# 464421_22-01_RF_Interface.net
KiCad netlist of a schematic drawn in Altium Designer
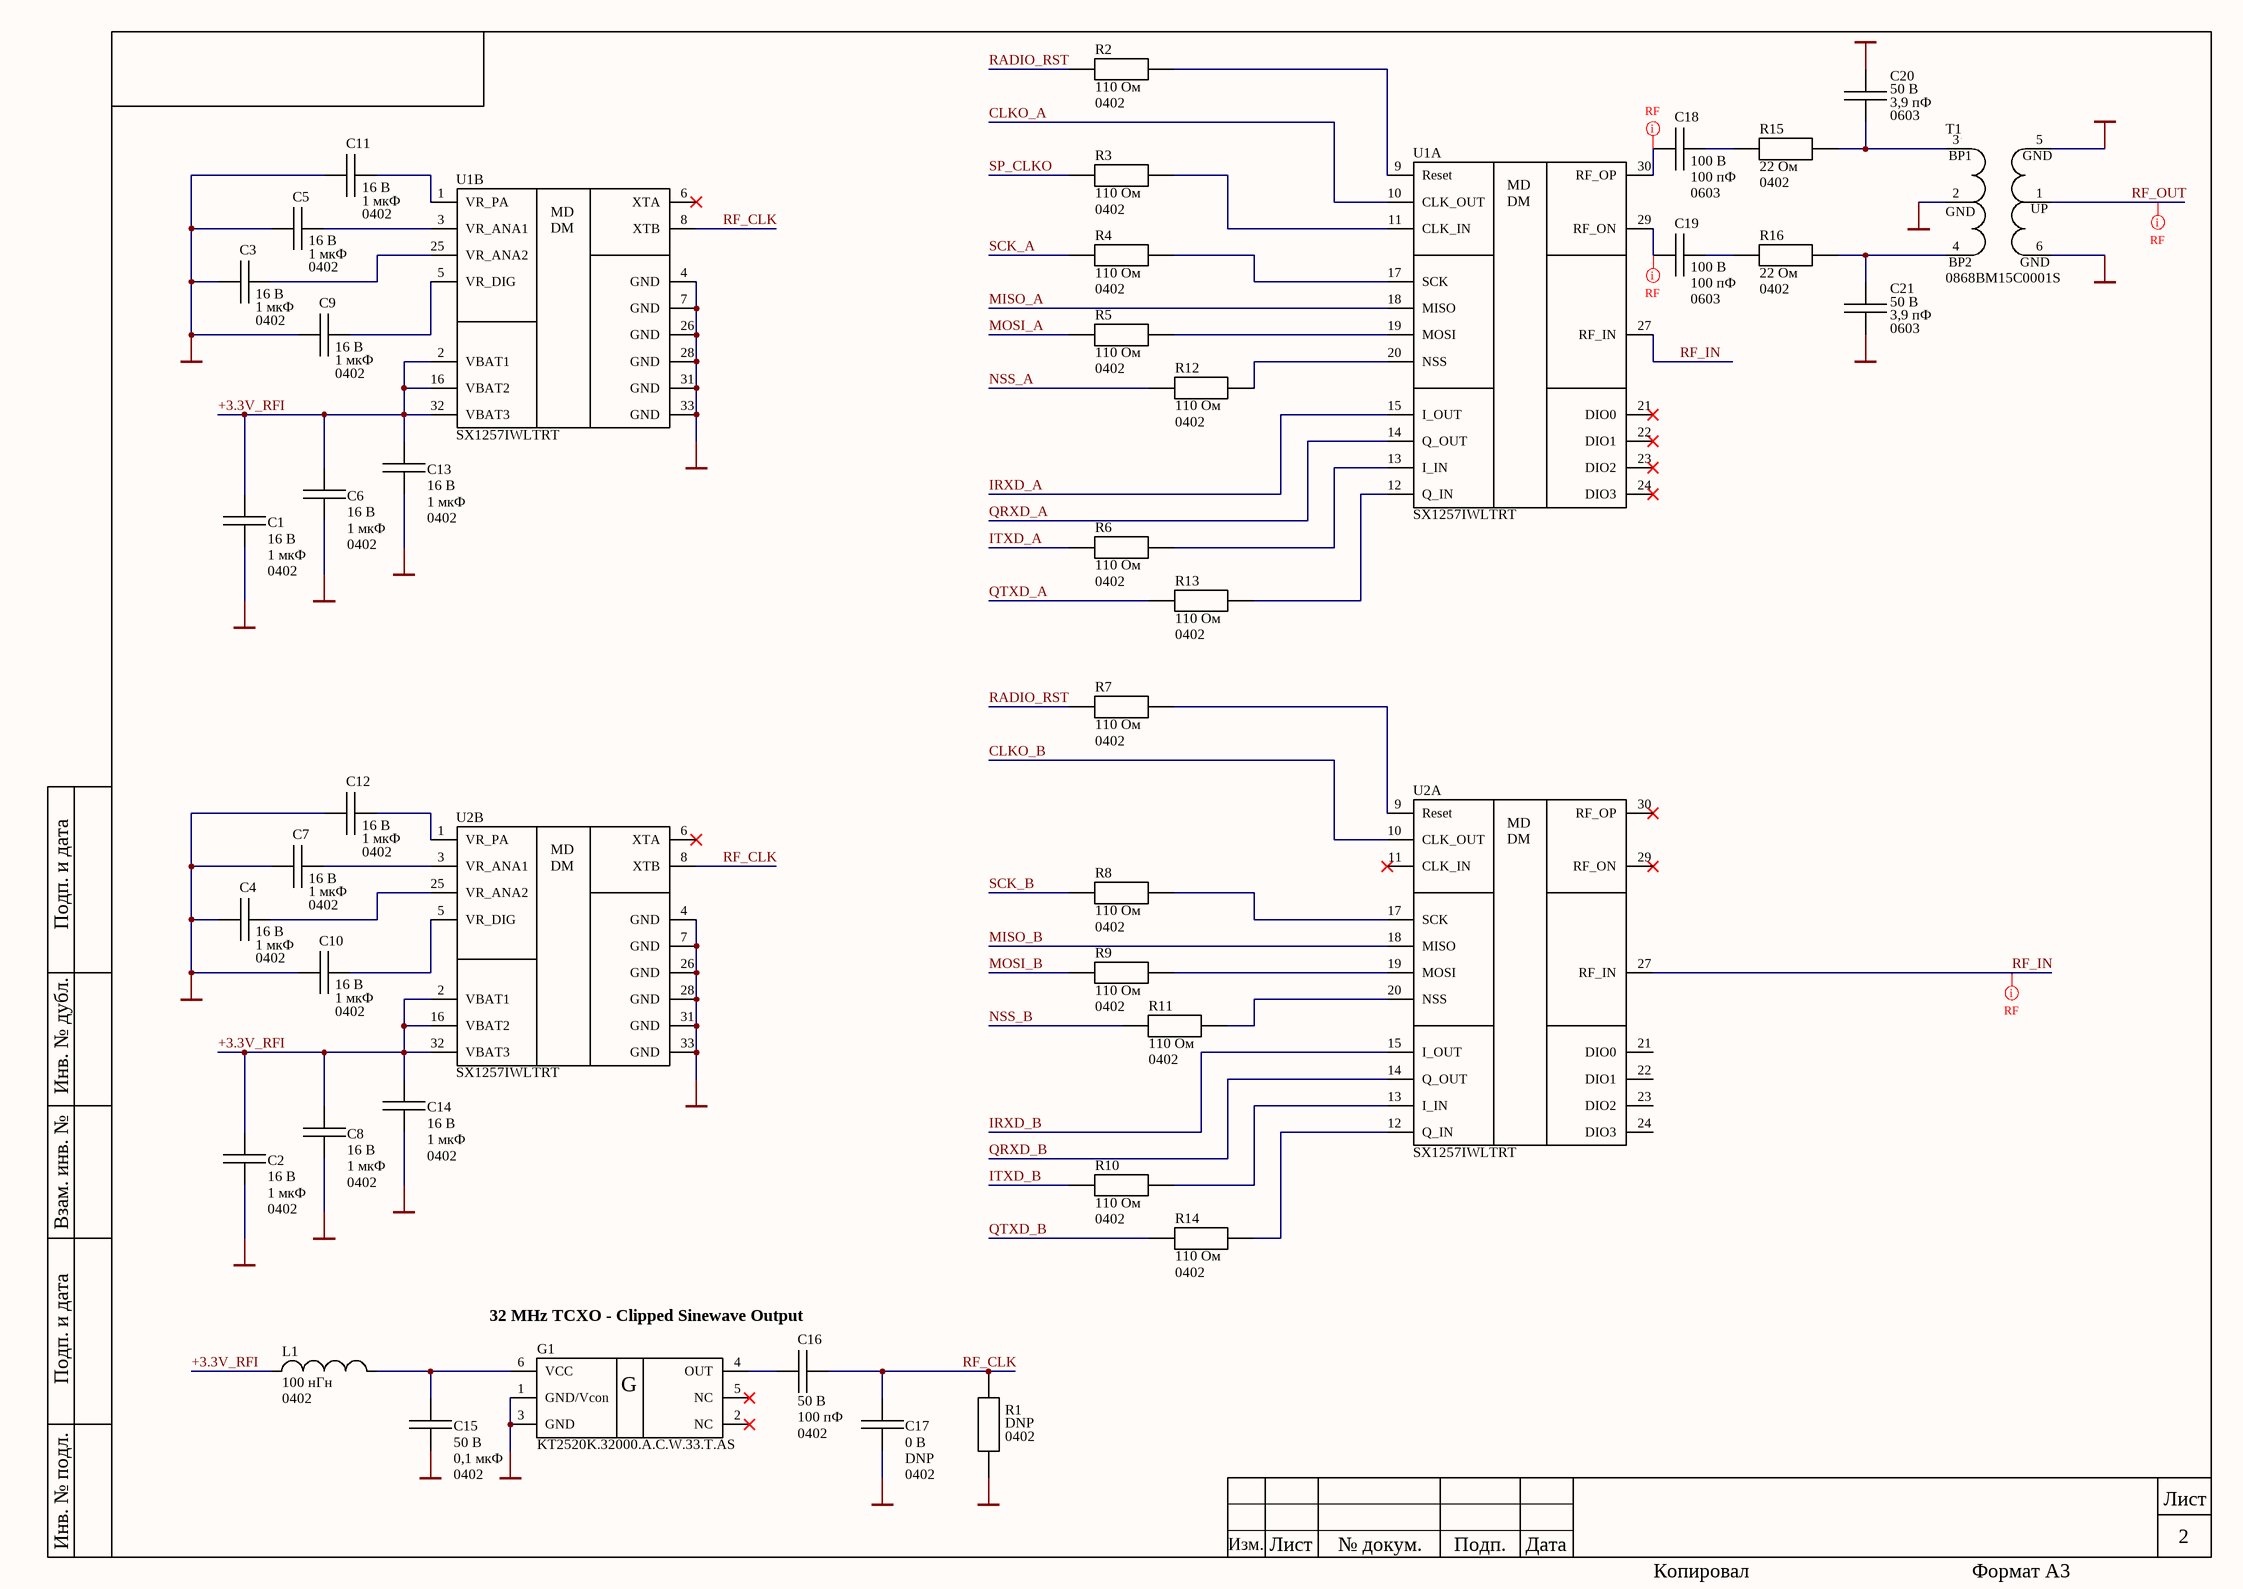
[diagram p0: МПСУ.464421.22-01 RF Interface.SchDoc]

(export (version "E")
  (design (tool "Eeschema 10.0.6"))
  (components
    (comp (ref "C1")
      (value "1 мкФ")
      (footprint "Passive_V2_0:CAPC100X50X55L20N")
      (description "Capacitor 0402")
      (fields
        (field (name "PARTNUMBER") "GRM155R61C105KA12D")
        (field (name "MANUFACTURER") "Murata")
        (field (name "PEAK_CONDITION") "16 В")
        (field (name "PACKAGE") "0402")
        (field (name "DESIGNER") "Свидерский")
      )
      (libsource (lib "Passive_V2_0") (part "C 0402"))
    )
    (comp (ref "C2")
      (value "1 мкФ")
      (footprint "Passive_V2_0:CAPC100X50X55L20N")
      (description "Capacitor 0402")
      (fields
        (field (name "PARTNUMBER") "GRM155R61C105KA12D")
        (field (name "MANUFACTURER") "Murata")
        (field (name "PEAK_CONDITION") "16 В")
        (field (name "PACKAGE") "0402")
        (field (name "DESIGNER") "Свидерский")
      )
      (libsource (lib "Passive_V2_0") (part "C 0402"))
    )
    (comp (ref "C3")
      (value "1 мкФ")
      (footprint "Passive_V2_0:CAPC100X50X55L20N")
      (description "Capacitor 0402")
      (fields
        (field (name "PARTNUMBER") "GRM155R61C105KA12D")
        (field (name "MANUFACTURER") "Murata")
        (field (name "PEAK_CONDITION") "16 В")
        (field (name "PACKAGE") "0402")
        (field (name "DESIGNER") "Свидерский")
      )
      (libsource (lib "Passive_V2_0") (part "C 0402"))
    )
    (comp (ref "C4")
      (value "1 мкФ")
      (footprint "Passive_V2_0:CAPC100X50X55L20N")
      (description "Capacitor 0402")
      (fields
        (field (name "PARTNUMBER") "GRM155R61C105KA12D")
        (field (name "MANUFACTURER") "Murata")
        (field (name "PEAK_CONDITION") "16 В")
        (field (name "PACKAGE") "0402")
        (field (name "DESIGNER") "Свидерский")
      )
      (libsource (lib "Passive_V2_0") (part "C 0402"))
    )
    (comp (ref "C5")
      (value "1 мкФ")
      (footprint "Passive_V2_0:CAPC100X50X55L20N")
      (description "Capacitor 0402")
      (fields
        (field (name "PARTNUMBER") "GRM155R61C105KA12D")
        (field (name "MANUFACTURER") "Murata")
        (field (name "PEAK_CONDITION") "16 В")
        (field (name "PACKAGE") "0402")
        (field (name "DESIGNER") "Свидерский")
      )
      (libsource (lib "Passive_V2_0") (part "C 0402"))
    )
    (comp (ref "C6")
      (value "1 мкФ")
      (footprint "Passive_V2_0:CAPC100X50X55L20N")
      (description "Capacitor 0402")
      (fields
        (field (name "PARTNUMBER") "GRM155R61C105KA12D")
        (field (name "MANUFACTURER") "Murata")
        (field (name "PEAK_CONDITION") "16 В")
        (field (name "PACKAGE") "0402")
        (field (name "DESIGNER") "Свидерский")
      )
      (libsource (lib "Passive_V2_0") (part "C 0402"))
    )
    (comp (ref "C7")
      (value "1 мкФ")
      (footprint "Passive_V2_0:CAPC100X50X55L20N")
      (description "Capacitor 0402")
      (fields
        (field (name "PARTNUMBER") "GRM155R61C105KA12D")
        (field (name "MANUFACTURER") "Murata")
        (field (name "PEAK_CONDITION") "16 В")
        (field (name "PACKAGE") "0402")
        (field (name "DESIGNER") "Свидерский")
      )
      (libsource (lib "Passive_V2_0") (part "C 0402"))
    )
    (comp (ref "C8")
      (value "1 мкФ")
      (footprint "Passive_V2_0:CAPC100X50X55L20N")
      (description "Capacitor 0402")
      (fields
        (field (name "PARTNUMBER") "GRM155R61C105KA12D")
        (field (name "MANUFACTURER") "Murata")
        (field (name "PEAK_CONDITION") "16 В")
        (field (name "PACKAGE") "0402")
        (field (name "DESIGNER") "Свидерский")
      )
      (libsource (lib "Passive_V2_0") (part "C 0402"))
    )
    (comp (ref "C9")
      (value "1 мкФ")
      (footprint "Passive_V2_0:CAPC100X50X55L20N")
      (description "Capacitor 0402")
      (fields
        (field (name "PARTNUMBER") "GRM155R61C105KA12D")
        (field (name "MANUFACTURER") "Murata")
        (field (name "PEAK_CONDITION") "16 В")
        (field (name "PACKAGE") "0402")
        (field (name "DESIGNER") "Свидерский")
      )
      (libsource (lib "Passive_V2_0") (part "C 0402"))
    )
    (comp (ref "C10")
      (value "1 мкФ")
      (footprint "Passive_V2_0:CAPC100X50X55L20N")
      (description "Capacitor 0402")
      (fields
        (field (name "PARTNUMBER") "GRM155R61C105KA12D")
        (field (name "MANUFACTURER") "Murata")
        (field (name "PEAK_CONDITION") "16 В")
        (field (name "PACKAGE") "0402")
        (field (name "DESIGNER") "Свидерский")
      )
      (libsource (lib "Passive_V2_0") (part "C 0402"))
    )
    (comp (ref "C11")
      (value "1 мкФ")
      (footprint "Passive_V2_0:CAPC100X50X55L20N")
      (description "Capacitor 0402")
      (fields
        (field (name "PARTNUMBER") "GRM155R61C105KA12D")
        (field (name "MANUFACTURER") "Murata")
        (field (name "PEAK_CONDITION") "16 В")
        (field (name "PACKAGE") "0402")
        (field (name "DESIGNER") "Свидерский")
      )
      (libsource (lib "Passive_V2_0") (part "C 0402"))
    )
    (comp (ref "C12")
      (value "1 мкФ")
      (footprint "Passive_V2_0:CAPC100X50X55L20N")
      (description "Capacitor 0402")
      (fields
        (field (name "PARTNUMBER") "GRM155R61C105KA12D")
        (field (name "MANUFACTURER") "Murata")
        (field (name "PEAK_CONDITION") "16 В")
        (field (name "PACKAGE") "0402")
        (field (name "DESIGNER") "Свидерский")
      )
      (libsource (lib "Passive_V2_0") (part "C 0402"))
    )
    (comp (ref "C13")
      (value "1 мкФ")
      (footprint "Passive_V2_0:CAPC100X50X55L20N")
      (description "Capacitor 0402")
      (fields
        (field (name "PARTNUMBER") "GRM155R61C105KA12D")
        (field (name "MANUFACTURER") "Murata")
        (field (name "PEAK_CONDITION") "16 В")
        (field (name "PACKAGE") "0402")
        (field (name "DESIGNER") "Свидерский")
      )
      (libsource (lib "Passive_V2_0") (part "C 0402"))
    )
    (comp (ref "C14")
      (value "1 мкФ")
      (footprint "Passive_V2_0:CAPC100X50X55L20N")
      (description "Capacitor 0402")
      (fields
        (field (name "PARTNUMBER") "GRM155R61C105KA12D")
        (field (name "MANUFACTURER") "Murata")
        (field (name "PEAK_CONDITION") "16 В")
        (field (name "PACKAGE") "0402")
        (field (name "DESIGNER") "Свидерский")
      )
      (libsource (lib "Passive_V2_0") (part "C 0402"))
    )
    (comp (ref "C15")
      (value "0,1 мкФ")
      (footprint "Passive_V2_0:CAPC100X50X55L20N")
      (description "Capacitor 0402")
      (fields
        (field (name "PARTNUMBER") "GRM155R71H104KE14J")
        (field (name "MANUFACTURER") "Murata")
        (field (name "PEAK_CONDITION") "50 В")
        (field (name "PACKAGE") "0402")
        (field (name "DESIGNER") "Свидерский")
      )
      (libsource (lib "Passive_V2_0") (part "C 0402"))
    )
    (comp (ref "C16")
      (value "100 пФ")
      (footprint "Passive_V2_0:CAPC100X50X55L20N")
      (description "Capacitor 0402")
      (fields
        (field (name "PARTNUMBER") "GRM1555C1H101JZ01D")
        (field (name "MANUFACTURER") "Murata")
        (field (name "PEAK_CONDITION") "50 В")
        (field (name "PACKAGE") "0402")
        (field (name "DESIGNER") "Свидерский")
      )
      (libsource (lib "Passive_V2_0") (part "C 0402"))
    )
    (comp (ref "C17")
      (value "DNP")
      (footprint "Passive_V2_0:CAPC100X50X55L20N")
      (description "Capacitor 0402")
      (fields
        (field (name "TOLERANCE") "0 %")
        (field (name "PEAK_CONDITION") "0 В")
        (field (name "PACKAGE") "0402")
        (field (name "Comment") "DNP 0402")
        (field (name "DESIGNER") "Свидерский")
      )
      (libsource (lib "Passive_V2_0") (part "C 0402"))
    )
    (comp (ref "C18")
      (value "100 пФ")
      (footprint "Passive_V2_0:CAPC160X80X90L30N")
      (description "Capacitor 0603")
      (fields
        (field (name "PARTNUMBER") "GRM1885C2A101FA01D")
        (field (name "MANUFACTURER") "Murata")
        (field (name "PEAK_CONDITION") "100 В")
        (field (name "PACKAGE") "0603")
        (field (name "DESIGNER") "Свидерский")
      )
      (libsource (lib "Passive_V2_0") (part "C 0603"))
    )
    (comp (ref "C19")
      (value "100 пФ")
      (footprint "Passive_V2_0:CAPC160X80X90L30N")
      (description "Capacitor 0603")
      (fields
        (field (name "PARTNUMBER") "GRM1885C2A101FA01D")
        (field (name "MANUFACTURER") "Murata")
        (field (name "PEAK_CONDITION") "100 В")
        (field (name "PACKAGE") "0603")
        (field (name "DESIGNER") "Свидерский")
      )
      (libsource (lib "Passive_V2_0") (part "C 0603"))
    )
    (comp (ref "C20")
      (value "3,9 пФ")
      (footprint "Passive_V2_0:CAPC160X80X90L30N")
      (description "Capacitor 0603")
      (fields
        (field (name "PARTNUMBER") "GRM1885C1H3R9CZ01D")
        (field (name "MANUFACTURER") "Murata")
        (field (name "PEAK_CONDITION") "50 В")
        (field (name "PACKAGE") "0603")
        (field (name "DESIGNER") "Свидерский")
      )
      (libsource (lib "Passive_V2_0") (part "C 0603"))
    )
    (comp (ref "C21")
      (value "3,9 пФ")
      (footprint "Passive_V2_0:CAPC160X80X90L30N")
      (description "Capacitor 0603")
      (fields
        (field (name "PARTNUMBER") "GRM1885C1H3R9CZ01D")
        (field (name "MANUFACTURER") "Murata")
        (field (name "PEAK_CONDITION") "50 В")
        (field (name "PACKAGE") "0603")
        (field (name "DESIGNER") "Свидерский")
      )
      (libsource (lib "Passive_V2_0") (part "C 0603"))
    )
    (comp (ref "G1")
      (value "KT2520K.32000.A.C.W.33.T.AS")
      (footprint "IC_V2_0:KT2520K")
      (description "Temperature Compensated Crystal Oscillators (TCXO, VCTCXO) Surface Mount Type")
      (fields
        (field (name "MANUFACTURER") "Kyocera")
        (field (name "PARTNUMBER") "KT2520K.32000.A.C.W.33.T.AS")
        (field (name "DESIGNER") "Лазба")
      )
      (libsource (lib "IC_V2_0") (part "KT2520K.*****.*.*.*.**.*.*"))
    )
    (comp (ref "L1")
      (value "100 нГн")
      (footprint "Passive_V2_0:INDC100X50X60L10N")
      (description "Inductor 0402")
      (fields
        (field (name "PARTNUMBER") "LQG15HNR10J02D")
        (field (name "TOLERANCE") "5 %")
        (field (name "PACKAGE") "0402")
        (field (name "DESIGNER") "Свидерский")
      )
      (libsource (lib "Passive_V2_0") (part "L 0402"))
    )
    (comp (ref "R1")
      (value "DNP")
      (footprint "Passive_V2_0:RESC100X50X40L25N")
      (description "Resistor 0402")
      (fields
        (field (name "TOLERANCE") "0 %")
        (field (name "PACKAGE") "0402")
        (field (name "Comment") "DNP 0402")
        (field (name "DESIGNER") "Свидерский")
      )
      (libsource (lib "") (part "R 0402_1"))
    )
    (comp (ref "R2")
      (value "110 Ом")
      (footprint "Passive_V2_0:RESC100X50X40L25N")
      (description "Resistor 0402")
      (fields
        (field (name "PARTNUMBER") "RC-02U111JT")
        (field (name "TOLERANCE") "5 %")
        (field (name "PACKAGE") "0402")
        (field (name "DESIGNER") "Свидерский")
      )
      (libsource (lib "Passive_V2_0") (part "R 0402"))
    )
    (comp (ref "R3")
      (value "110 Ом")
      (footprint "Passive_V2_0:RESC100X50X40L25N")
      (description "Resistor 0402")
      (fields
        (field (name "PARTNUMBER") "RC-02U111JT")
        (field (name "TOLERANCE") "5 %")
        (field (name "PACKAGE") "0402")
        (field (name "DESIGNER") "Свидерский")
      )
      (libsource (lib "Passive_V2_0") (part "R 0402"))
    )
    (comp (ref "R4")
      (value "110 Ом")
      (footprint "Passive_V2_0:RESC100X50X40L25N")
      (description "Resistor 0402")
      (fields
        (field (name "PARTNUMBER") "RC-02U111JT")
        (field (name "TOLERANCE") "5 %")
        (field (name "PACKAGE") "0402")
        (field (name "DESIGNER") "Свидерский")
      )
      (libsource (lib "Passive_V2_0") (part "R 0402"))
    )
    (comp (ref "R5")
      (value "110 Ом")
      (footprint "Passive_V2_0:RESC100X50X40L25N")
      (description "Resistor 0402")
      (fields
        (field (name "PARTNUMBER") "RC-02U111JT")
        (field (name "TOLERANCE") "5 %")
        (field (name "PACKAGE") "0402")
        (field (name "DESIGNER") "Свидерский")
      )
      (libsource (lib "Passive_V2_0") (part "R 0402"))
    )
    (comp (ref "R6")
      (value "110 Ом")
      (footprint "Passive_V2_0:RESC100X50X40L25N")
      (description "Resistor 0402")
      (fields
        (field (name "PARTNUMBER") "RC-02U111JT")
        (field (name "TOLERANCE") "5 %")
        (field (name "PACKAGE") "0402")
        (field (name "DESIGNER") "Свидерский")
      )
      (libsource (lib "Passive_V2_0") (part "R 0402"))
    )
    (comp (ref "R7")
      (value "110 Ом")
      (footprint "Passive_V2_0:RESC100X50X40L25N")
      (description "Resistor 0402")
      (fields
        (field (name "PARTNUMBER") "RC-02U111JT")
        (field (name "TOLERANCE") "5 %")
        (field (name "PACKAGE") "0402")
        (field (name "DESIGNER") "Свидерский")
      )
      (libsource (lib "Passive_V2_0") (part "R 0402"))
    )
    (comp (ref "R8")
      (value "110 Ом")
      (footprint "Passive_V2_0:RESC100X50X40L25N")
      (description "Resistor 0402")
      (fields
        (field (name "PARTNUMBER") "RC-02U111JT")
        (field (name "TOLERANCE") "5 %")
        (field (name "PACKAGE") "0402")
        (field (name "DESIGNER") "Свидерский")
      )
      (libsource (lib "Passive_V2_0") (part "R 0402"))
    )
    (comp (ref "R9")
      (value "110 Ом")
      (footprint "Passive_V2_0:RESC100X50X40L25N")
      (description "Resistor 0402")
      (fields
        (field (name "PARTNUMBER") "RC-02U111JT")
        (field (name "TOLERANCE") "5 %")
        (field (name "PACKAGE") "0402")
        (field (name "DESIGNER") "Свидерский")
      )
      (libsource (lib "Passive_V2_0") (part "R 0402"))
    )
    (comp (ref "R10")
      (value "110 Ом")
      (footprint "Passive_V2_0:RESC100X50X40L25N")
      (description "Resistor 0402")
      (fields
        (field (name "PARTNUMBER") "RC-02U111JT")
        (field (name "TOLERANCE") "5 %")
        (field (name "PACKAGE") "0402")
        (field (name "DESIGNER") "Свидерский")
      )
      (libsource (lib "Passive_V2_0") (part "R 0402"))
    )
    (comp (ref "R11")
      (value "110 Ом")
      (footprint "Passive_V2_0:RESC100X50X40L25N")
      (description "Resistor 0402")
      (fields
        (field (name "PARTNUMBER") "RC-02U111JT")
        (field (name "TOLERANCE") "5 %")
        (field (name "PACKAGE") "0402")
        (field (name "DESIGNER") "Свидерский")
      )
      (libsource (lib "Passive_V2_0") (part "R 0402"))
    )
    (comp (ref "R12")
      (value "110 Ом")
      (footprint "Passive_V2_0:RESC100X50X40L25N")
      (description "Resistor 0402")
      (fields
        (field (name "PARTNUMBER") "RC-02U111JT")
        (field (name "TOLERANCE") "5 %")
        (field (name "PACKAGE") "0402")
        (field (name "DESIGNER") "Свидерский")
      )
      (libsource (lib "Passive_V2_0") (part "R 0402"))
    )
    (comp (ref "R13")
      (value "110 Ом")
      (footprint "Passive_V2_0:RESC100X50X40L25N")
      (description "Resistor 0402")
      (fields
        (field (name "PARTNUMBER") "RC-02U111JT")
        (field (name "TOLERANCE") "5 %")
        (field (name "PACKAGE") "0402")
        (field (name "DESIGNER") "Свидерский")
      )
      (libsource (lib "Passive_V2_0") (part "R 0402"))
    )
    (comp (ref "R14")
      (value "110 Ом")
      (footprint "Passive_V2_0:RESC100X50X40L25N")
      (description "Resistor 0402")
      (fields
        (field (name "PARTNUMBER") "RC-02U111JT")
        (field (name "TOLERANCE") "5 %")
        (field (name "PACKAGE") "0402")
        (field (name "DESIGNER") "Свидерский")
      )
      (libsource (lib "Passive_V2_0") (part "R 0402"))
    )
    (comp (ref "R15")
      (value "22 Ом")
      (footprint "Passive_V2_0:RESC100X50X40L25N")
      (description "Resistor 0402")
      (fields
        (field (name "PARTNUMBER") "RC0402FR-0722RL")
        (field (name "TOLERANCE") "1 %")
        (field (name "PACKAGE") "0402")
        (field (name "DESIGNER") "Свидерский")
      )
      (libsource (lib "Passive_V2_0") (part "R 0402"))
    )
    (comp (ref "R16")
      (value "22 Ом")
      (footprint "Passive_V2_0:RESC100X50X40L25N")
      (description "Resistor 0402")
      (fields
        (field (name "PARTNUMBER") "RC0402FR-0722RL")
        (field (name "TOLERANCE") "1 %")
        (field (name "PACKAGE") "0402")
        (field (name "DESIGNER") "Свидерский")
      )
      (libsource (lib "Passive_V2_0") (part "R 0402"))
    )
    (comp (ref "T1")
      (value "0868BM15C0001S")
      (footprint "Passive_V2_0:LCC065P125X200X085-6")
      (fields
        (field (name "MANUFACTURER") "Johanson Technology Inc.")
        (field (name "PARTNUMBER") "0868BM15C0001S")
        (field (name "DESIGNER") "Лазба")
      )
      (libsource (lib "Passive_V2_0") (part "0868BM15C0001*"))
    )
    (comp (ref "U1")
      (value "SX1257IWLTRT")
      (footprint "IC_V2_0:SX1257IWLTRT")
      (description "LoRa Core™ Low Power Digital I and Q RF Multi-PHY Mode Analog Front End 860-1000MHz")
      (fields
        (field (name "MANUFACTURER") "Semtech")
        (field (name "PARTNUMBER") "SX1257IWLTRT")
        (field (name "DESIGNER") "Лазба")
      )
      (libsource (lib "") (part "SX1257IWLTRT_1"))
    )
    (comp (ref "U2")
      (value "SX1257IWLTRT")
      (footprint "IC_V2_0:SX1257IWLTRT")
      (description "LoRa Core™ Low Power Digital I and Q RF Multi-PHY Mode Analog Front End 860-1000MHz")
      (fields
        (field (name "MANUFACTURER") "Semtech")
        (field (name "PARTNUMBER") "SX1257IWLTRT")
        (field (name "DESIGNER") "Лазба")
      )
      (libsource (lib "IC_V2_0") (part "SX1257IWLTRT"))
    )
  )
  (nets
    (net (code "1") (name "/+3.3V_RFI") (class "Default")
      (node (ref "C1") (pin "2") (pinfunction "2_2") (pintype "passive"))
      (node (ref "C13") (pin "2") (pinfunction "2_2") (pintype "passive"))
      (node (ref "C14") (pin "2") (pinfunction "2_2") (pintype "passive"))
      (node (ref "C2") (pin "2") (pinfunction "2_2") (pintype "passive"))
      (node (ref "C6") (pin "2") (pinfunction "2_2") (pintype "passive"))
      (node (ref "C8") (pin "2") (pinfunction "2_2") (pintype "passive"))
      (node (ref "L1") (pin "1") (pinfunction "1_1") (pintype "passive"))
      (node (ref "U1") (pin "16") (pinfunction "VBAT2_16") (pintype "passive"))
      (node (ref "U1") (pin "2") (pinfunction "VBAT1_2") (pintype "passive"))
      (node (ref "U1") (pin "32") (pinfunction "VBAT3_32") (pintype "passive"))
      (node (ref "U2") (pin "16") (pinfunction "VBAT2_16") (pintype "passive"))
      (node (ref "U2") (pin "2") (pinfunction "VBAT1_2") (pintype "passive"))
      (node (ref "U2") (pin "32") (pinfunction "VBAT3_32") (pintype "passive"))
    )
    (net (code "2") (name "/CLKO_A") (class "Default")
      (node (ref "U1") (pin "10") (pinfunction "CLK_OUT_10") (pintype "passive"))
    )
    (net (code "3") (name "/CLKO_B") (class "Default")
      (node (ref "U2") (pin "10") (pinfunction "CLK_OUT_10") (pintype "passive"))
    )
    (net (code "4") (name "/IRXD_A") (class "Default")
      (node (ref "U1") (pin "15") (pinfunction "I_OUT_15") (pintype "passive"))
    )
    (net (code "5") (name "/IRXD_B") (class "Default")
      (node (ref "U2") (pin "15") (pinfunction "I_OUT_15") (pintype "passive"))
    )
    (net (code "6") (name "/ITXD_A") (class "Default")
      (node (ref "R6") (pin "1") (pinfunction "1_1") (pintype "passive"))
    )
    (net (code "7") (name "/ITXD_B") (class "Default")
      (node (ref "R10") (pin "1") (pinfunction "1_1") (pintype "passive"))
    )
    (net (code "8") (name "/MISO_A") (class "Default")
      (node (ref "U1") (pin "18") (pinfunction "MISO_18") (pintype "passive"))
    )
    (net (code "9") (name "/MISO_B") (class "Default")
      (node (ref "U2") (pin "18") (pinfunction "MISO_18") (pintype "passive"))
    )
    (net (code "10") (name "/MOSI_A") (class "Default")
      (node (ref "R5") (pin "1") (pinfunction "1_1") (pintype "passive"))
    )
    (net (code "11") (name "/MOSI_B") (class "Default")
      (node (ref "R9") (pin "1") (pinfunction "1_1") (pintype "passive"))
    )
    (net (code "12") (name "/NSS_A") (class "Default")
      (node (ref "R12") (pin "1") (pinfunction "1_1") (pintype "passive"))
    )
    (net (code "13") (name "/NSS_B") (class "Default")
      (node (ref "R11") (pin "1") (pinfunction "1_1") (pintype "passive"))
    )
    (net (code "14") (name "/QRXD_A") (class "Default")
      (node (ref "U1") (pin "14") (pinfunction "Q_OUT_14") (pintype "passive"))
    )
    (net (code "15") (name "/QRXD_B") (class "Default")
      (node (ref "U2") (pin "14") (pinfunction "Q_OUT_14") (pintype "passive"))
    )
    (net (code "16") (name "/QTXD_A") (class "Default")
      (node (ref "R13") (pin "1") (pinfunction "1_1") (pintype "passive"))
    )
    (net (code "17") (name "/QTXD_B") (class "Default")
      (node (ref "R14") (pin "1") (pinfunction "1_1") (pintype "passive"))
    )
    (net (code "18") (name "/RADIO_RST") (class "Default")
      (node (ref "R2") (pin "1") (pinfunction "1_1") (pintype "passive"))
      (node (ref "R7") (pin "1") (pinfunction "1_1") (pintype "passive"))
    )
    (net (code "19") (name "/RF_CLK") (class "Default")
      (node (ref "C16") (pin "2") (pinfunction "2_2") (pintype "passive"))
      (node (ref "C17") (pin "1") (pinfunction "1_1") (pintype "passive"))
      (node (ref "R1") (pin "1") (pinfunction "1_1") (pintype "passive"))
      (node (ref "U1") (pin "8") (pinfunction "XTB_8") (pintype "passive"))
      (node (ref "U2") (pin "8") (pinfunction "XTB_8") (pintype "passive"))
    )
    (net (code "20") (name "/RF_IN") (class "Default")
      (node (ref "U1") (pin "27") (pinfunction "RF_IN_27") (pintype "passive"))
      (node (ref "U2") (pin "27") (pinfunction "RF_IN_27") (pintype "passive"))
    )
    (net (code "21") (name "/RF_OUT") (class "Default")
      (node (ref "T1") (pin "1") (pinfunction "UP_1") (pintype "passive"))
    )
    (net (code "22") (name "/SCK_A") (class "Default")
      (node (ref "R4") (pin "1") (pinfunction "1_1") (pintype "passive"))
    )
    (net (code "23") (name "/SCK_B") (class "Default")
      (node (ref "R8") (pin "1") (pinfunction "1_1") (pintype "passive"))
    )
    (net (code "24") (name "/SP_CLKO") (class "Default")
      (node (ref "R3") (pin "1") (pinfunction "1_1") (pintype "passive"))
    )
    (net (code "25") (name "GND") (class "Default")
      (node (ref "C1") (pin "1") (pinfunction "1_1") (pintype "passive"))
      (node (ref "C10") (pin "2") (pinfunction "2_2") (pintype "passive"))
      (node (ref "C11") (pin "2") (pinfunction "2_2") (pintype "passive"))
      (node (ref "C12") (pin "2") (pinfunction "2_2") (pintype "passive"))
      (node (ref "C13") (pin "1") (pinfunction "1_1") (pintype "passive"))
      (node (ref "C14") (pin "1") (pinfunction "1_1") (pintype "passive"))
      (node (ref "C15") (pin "2") (pinfunction "2_2") (pintype "passive"))
      (node (ref "C17") (pin "2") (pinfunction "2_2") (pintype "passive"))
      (node (ref "C2") (pin "1") (pinfunction "1_1") (pintype "passive"))
      (node (ref "C20") (pin "1") (pinfunction "1_1") (pintype "passive"))
      (node (ref "C21") (pin "2") (pinfunction "2_2") (pintype "passive"))
      (node (ref "C3") (pin "2") (pinfunction "2_2") (pintype "passive"))
      (node (ref "C4") (pin "2") (pinfunction "2_2") (pintype "passive"))
      (node (ref "C5") (pin "2") (pinfunction "2_2") (pintype "passive"))
      (node (ref "C6") (pin "1") (pinfunction "1_1") (pintype "passive"))
      (node (ref "C7") (pin "2") (pinfunction "2_2") (pintype "passive"))
      (node (ref "C8") (pin "1") (pinfunction "1_1") (pintype "passive"))
      (node (ref "C9") (pin "2") (pinfunction "2_2") (pintype "passive"))
      (node (ref "G1") (pin "1") (pinfunction "GND/Vcon_1") (pintype "passive"))
      (node (ref "G1") (pin "3") (pinfunction "GND_3") (pintype "passive"))
      (node (ref "R1") (pin "2") (pinfunction "2_2") (pintype "passive"))
      (node (ref "T1") (pin "2") (pinfunction "GND_2") (pintype "passive"))
      (node (ref "T1") (pin "5") (pinfunction "GND_5") (pintype "passive"))
      (node (ref "T1") (pin "6") (pinfunction "GND_6") (pintype "passive"))
      (node (ref "U1") (pin "26") (pinfunction "GND_26") (pintype "passive"))
      (node (ref "U1") (pin "28") (pinfunction "GND_28") (pintype "passive"))
      (node (ref "U1") (pin "31") (pinfunction "GND_31") (pintype "passive"))
      (node (ref "U1") (pin "33") (pinfunction "GND_33") (pintype "passive"))
      (node (ref "U1") (pin "4") (pinfunction "GND_4") (pintype "passive"))
      (node (ref "U1") (pin "7") (pinfunction "GND_7") (pintype "passive"))
      (node (ref "U2") (pin "26") (pinfunction "GND_26") (pintype "passive"))
      (node (ref "U2") (pin "28") (pinfunction "GND_28") (pintype "passive"))
      (node (ref "U2") (pin "31") (pinfunction "GND_31") (pintype "passive"))
      (node (ref "U2") (pin "33") (pinfunction "GND_33") (pintype "passive"))
      (node (ref "U2") (pin "4") (pinfunction "GND_4") (pintype "passive"))
      (node (ref "U2") (pin "7") (pinfunction "GND_7") (pintype "passive"))
    )
    (net (code "26") (name "Net-(C18-Pad2)") (class "Default")
      (node (ref "C18") (pin "2") (pinfunction "2_2") (pintype "passive"))
      (node (ref "R15") (pin "1") (pinfunction "1_1") (pintype "passive"))
    )
    (net (code "27") (name "Net-(C19-Pad2)") (class "Default")
      (node (ref "C19") (pin "2") (pinfunction "2_2") (pintype "passive"))
      (node (ref "R16") (pin "1") (pinfunction "1_1") (pintype "passive"))
    )
    (net (code "28") (name "Net-(G1-OUT)") (class "Default")
      (node (ref "C16") (pin "1") (pinfunction "1_1") (pintype "passive"))
      (node (ref "G1") (pin "4") (pinfunction "OUT_4") (pintype "passive"))
    )
    (net (code "29") (name "Net-(G1-VCC)") (class "Default")
      (node (ref "C15") (pin "1") (pinfunction "1_1") (pintype "passive"))
      (node (ref "G1") (pin "6") (pinfunction "VCC_6") (pintype "passive"))
      (node (ref "L1") (pin "2") (pinfunction "2_2") (pintype "passive"))
    )
    (net (code "30") (name "Net-(T1-BP1)") (class "Default")
      (node (ref "C20") (pin "2") (pinfunction "2_2") (pintype "passive"))
      (node (ref "R15") (pin "2") (pinfunction "2_2") (pintype "passive"))
      (node (ref "T1") (pin "3") (pinfunction "BP1_3") (pintype "passive"))
    )
    (net (code "31") (name "Net-(T1-BP2)") (class "Default")
      (node (ref "C21") (pin "1") (pinfunction "1_1") (pintype "passive"))
      (node (ref "R16") (pin "2") (pinfunction "2_2") (pintype "passive"))
      (node (ref "T1") (pin "4") (pinfunction "BP2_4") (pintype "passive"))
    )
    (net (code "32") (name "Net-(U1A-CLK_IN)") (class "Default")
      (node (ref "R3") (pin "2") (pinfunction "2_2") (pintype "passive"))
      (node (ref "U1") (pin "11") (pinfunction "CLK_IN_11") (pintype "passive"))
    )
    (net (code "33") (name "Net-(U1A-I_IN)") (class "Default")
      (node (ref "R6") (pin "2") (pinfunction "2_2") (pintype "passive"))
      (node (ref "U1") (pin "13") (pinfunction "I_IN_13") (pintype "passive"))
    )
    (net (code "34") (name "Net-(U1A-MOSI)") (class "Default")
      (node (ref "R5") (pin "2") (pinfunction "2_2") (pintype "passive"))
      (node (ref "U1") (pin "19") (pinfunction "MOSI_19") (pintype "passive"))
    )
    (net (code "35") (name "Net-(U1A-NSS)") (class "Default")
      (node (ref "R12") (pin "2") (pinfunction "2_2") (pintype "passive"))
      (node (ref "U1") (pin "20") (pinfunction "NSS_20") (pintype "passive"))
    )
    (net (code "36") (name "Net-(U1A-Q_IN)") (class "Default")
      (node (ref "R13") (pin "2") (pinfunction "2_2") (pintype "passive"))
      (node (ref "U1") (pin "12") (pinfunction "Q_IN_12") (pintype "passive"))
    )
    (net (code "37") (name "Net-(U1A-RF_ON)") (class "Default")
      (node (ref "C19") (pin "1") (pinfunction "1_1") (pintype "passive"))
      (node (ref "U1") (pin "29") (pinfunction "RF_ON_29") (pintype "passive"))
    )
    (net (code "38") (name "Net-(U1A-RF_OP)") (class "Default")
      (node (ref "C18") (pin "1") (pinfunction "1_1") (pintype "passive"))
      (node (ref "U1") (pin "30") (pinfunction "RF_OP_30") (pintype "passive"))
    )
    (net (code "39") (name "Net-(U1A-Reset)") (class "Default")
      (node (ref "R2") (pin "2") (pinfunction "2_2") (pintype "passive"))
      (node (ref "U1") (pin "9") (pinfunction "Reset_9") (pintype "passive"))
    )
    (net (code "40") (name "Net-(U1A-SCK)") (class "Default")
      (node (ref "R4") (pin "2") (pinfunction "2_2") (pintype "passive"))
      (node (ref "U1") (pin "17") (pinfunction "SCK_17") (pintype "passive"))
    )
    (net (code "41") (name "Net-(U1B-VR_ANA1)") (class "Default")
      (node (ref "C5") (pin "1") (pinfunction "1_1") (pintype "passive"))
      (node (ref "U1") (pin "3") (pinfunction "VR_ANA1_3") (pintype "passive"))
    )
    (net (code "42") (name "Net-(U1B-VR_ANA2)") (class "Default")
      (node (ref "C3") (pin "1") (pinfunction "1_1") (pintype "passive"))
      (node (ref "U1") (pin "25") (pinfunction "VR_ANA2_25") (pintype "passive"))
    )
    (net (code "43") (name "Net-(U1B-VR_DIG)") (class "Default")
      (node (ref "C9") (pin "1") (pinfunction "1_1") (pintype "passive"))
      (node (ref "U1") (pin "5") (pinfunction "VR_DIG_5") (pintype "passive"))
    )
    (net (code "44") (name "Net-(U1B-VR_PA)") (class "Default")
      (node (ref "C11") (pin "1") (pinfunction "1_1") (pintype "passive"))
      (node (ref "U1") (pin "1") (pinfunction "VR_PA_1") (pintype "passive"))
    )
    (net (code "45") (name "Net-(U2A-I_IN)") (class "Default")
      (node (ref "R10") (pin "2") (pinfunction "2_2") (pintype "passive"))
      (node (ref "U2") (pin "13") (pinfunction "I_IN_13") (pintype "passive"))
    )
    (net (code "46") (name "Net-(U2A-MOSI)") (class "Default")
      (node (ref "R9") (pin "2") (pinfunction "2_2") (pintype "passive"))
      (node (ref "U2") (pin "19") (pinfunction "MOSI_19") (pintype "passive"))
    )
    (net (code "47") (name "Net-(U2A-NSS)") (class "Default")
      (node (ref "R11") (pin "2") (pinfunction "2_2") (pintype "passive"))
      (node (ref "U2") (pin "20") (pinfunction "NSS_20") (pintype "passive"))
    )
    (net (code "48") (name "Net-(U2A-Q_IN)") (class "Default")
      (node (ref "R14") (pin "2") (pinfunction "2_2") (pintype "passive"))
      (node (ref "U2") (pin "12") (pinfunction "Q_IN_12") (pintype "passive"))
    )
    (net (code "49") (name "Net-(U2A-Reset)") (class "Default")
      (node (ref "R7") (pin "2") (pinfunction "2_2") (pintype "passive"))
      (node (ref "U2") (pin "9") (pinfunction "Reset_9") (pintype "passive"))
    )
    (net (code "50") (name "Net-(U2A-SCK)") (class "Default")
      (node (ref "R8") (pin "2") (pinfunction "2_2") (pintype "passive"))
      (node (ref "U2") (pin "17") (pinfunction "SCK_17") (pintype "passive"))
    )
    (net (code "51") (name "Net-(U2B-VR_ANA1)") (class "Default")
      (node (ref "C7") (pin "1") (pinfunction "1_1") (pintype "passive"))
      (node (ref "U2") (pin "3") (pinfunction "VR_ANA1_3") (pintype "passive"))
    )
    (net (code "52") (name "Net-(U2B-VR_ANA2)") (class "Default")
      (node (ref "C4") (pin "1") (pinfunction "1_1") (pintype "passive"))
      (node (ref "U2") (pin "25") (pinfunction "VR_ANA2_25") (pintype "passive"))
    )
    (net (code "53") (name "Net-(U2B-VR_DIG)") (class "Default")
      (node (ref "C10") (pin "1") (pinfunction "1_1") (pintype "passive"))
      (node (ref "U2") (pin "5") (pinfunction "VR_DIG_5") (pintype "passive"))
    )
    (net (code "54") (name "Net-(U2B-VR_PA)") (class "Default")
      (node (ref "C12") (pin "1") (pinfunction "1_1") (pintype "passive"))
      (node (ref "U2") (pin "1") (pinfunction "VR_PA_1") (pintype "passive"))
    )
    (net (code "55") (name "unconnected-(G1-NC-Pad2)") (class "Default")
      (node (ref "G1") (pin "2") (pinfunction "NC_2") (pintype "passive+no_connect"))
    )
    (net (code "56") (name "unconnected-(G1-NC-Pad5)") (class "Default")
      (node (ref "G1") (pin "5") (pinfunction "NC_5") (pintype "passive+no_connect"))
    )
    (net (code "57") (name "unconnected-(U1A-DIO0-Pad21)") (class "Default")
      (node (ref "U1") (pin "21") (pinfunction "DIO0_21") (pintype "passive+no_connect"))
    )
    (net (code "58") (name "unconnected-(U1A-DIO1-Pad22)") (class "Default")
      (node (ref "U1") (pin "22") (pinfunction "DIO1_22") (pintype "passive+no_connect"))
    )
    (net (code "59") (name "unconnected-(U1A-DIO2-Pad23)") (class "Default")
      (node (ref "U1") (pin "23") (pinfunction "DIO2_23") (pintype "passive+no_connect"))
    )
    (net (code "60") (name "unconnected-(U1A-DIO3-Pad24)") (class "Default")
      (node (ref "U1") (pin "24") (pinfunction "DIO3_24") (pintype "passive+no_connect"))
    )
    (net (code "61") (name "unconnected-(U1B-XTA-Pad6)") (class "Default")
      (node (ref "U1") (pin "6") (pinfunction "XTA_6") (pintype "passive+no_connect"))
    )
    (net (code "62") (name "unconnected-(U2A-CLK_IN-Pad11)") (class "Default")
      (node (ref "U2") (pin "11") (pinfunction "CLK_IN_11") (pintype "passive+no_connect"))
    )
    (net (code "63") (name "unconnected-(U2A-DIO0-Pad21)") (class "Default")
      (node (ref "U2") (pin "21") (pinfunction "DIO0_21") (pintype "passive"))
    )
    (net (code "64") (name "unconnected-(U2A-DIO1-Pad22)") (class "Default")
      (node (ref "U2") (pin "22") (pinfunction "DIO1_22") (pintype "passive"))
    )
    (net (code "65") (name "unconnected-(U2A-DIO2-Pad23)") (class "Default")
      (node (ref "U2") (pin "23") (pinfunction "DIO2_23") (pintype "passive"))
    )
    (net (code "66") (name "unconnected-(U2A-DIO3-Pad24)") (class "Default")
      (node (ref "U2") (pin "24") (pinfunction "DIO3_24") (pintype "passive"))
    )
    (net (code "67") (name "unconnected-(U2A-RF_ON-Pad29)") (class "Default")
      (node (ref "U2") (pin "29") (pinfunction "RF_ON_29") (pintype "passive+no_connect"))
    )
    (net (code "68") (name "unconnected-(U2A-RF_OP-Pad30)") (class "Default")
      (node (ref "U2") (pin "30") (pinfunction "RF_OP_30") (pintype "passive+no_connect"))
    )
    (net (code "69") (name "unconnected-(U2B-XTA-Pad6)") (class "Default")
      (node (ref "U2") (pin "6") (pinfunction "XTA_6") (pintype "passive+no_connect"))
    )
  )
)
